# 51-2001-01-10_04_Power_Module_Schematic.net
KiCad netlist of a schematic drawn in Altium Designer
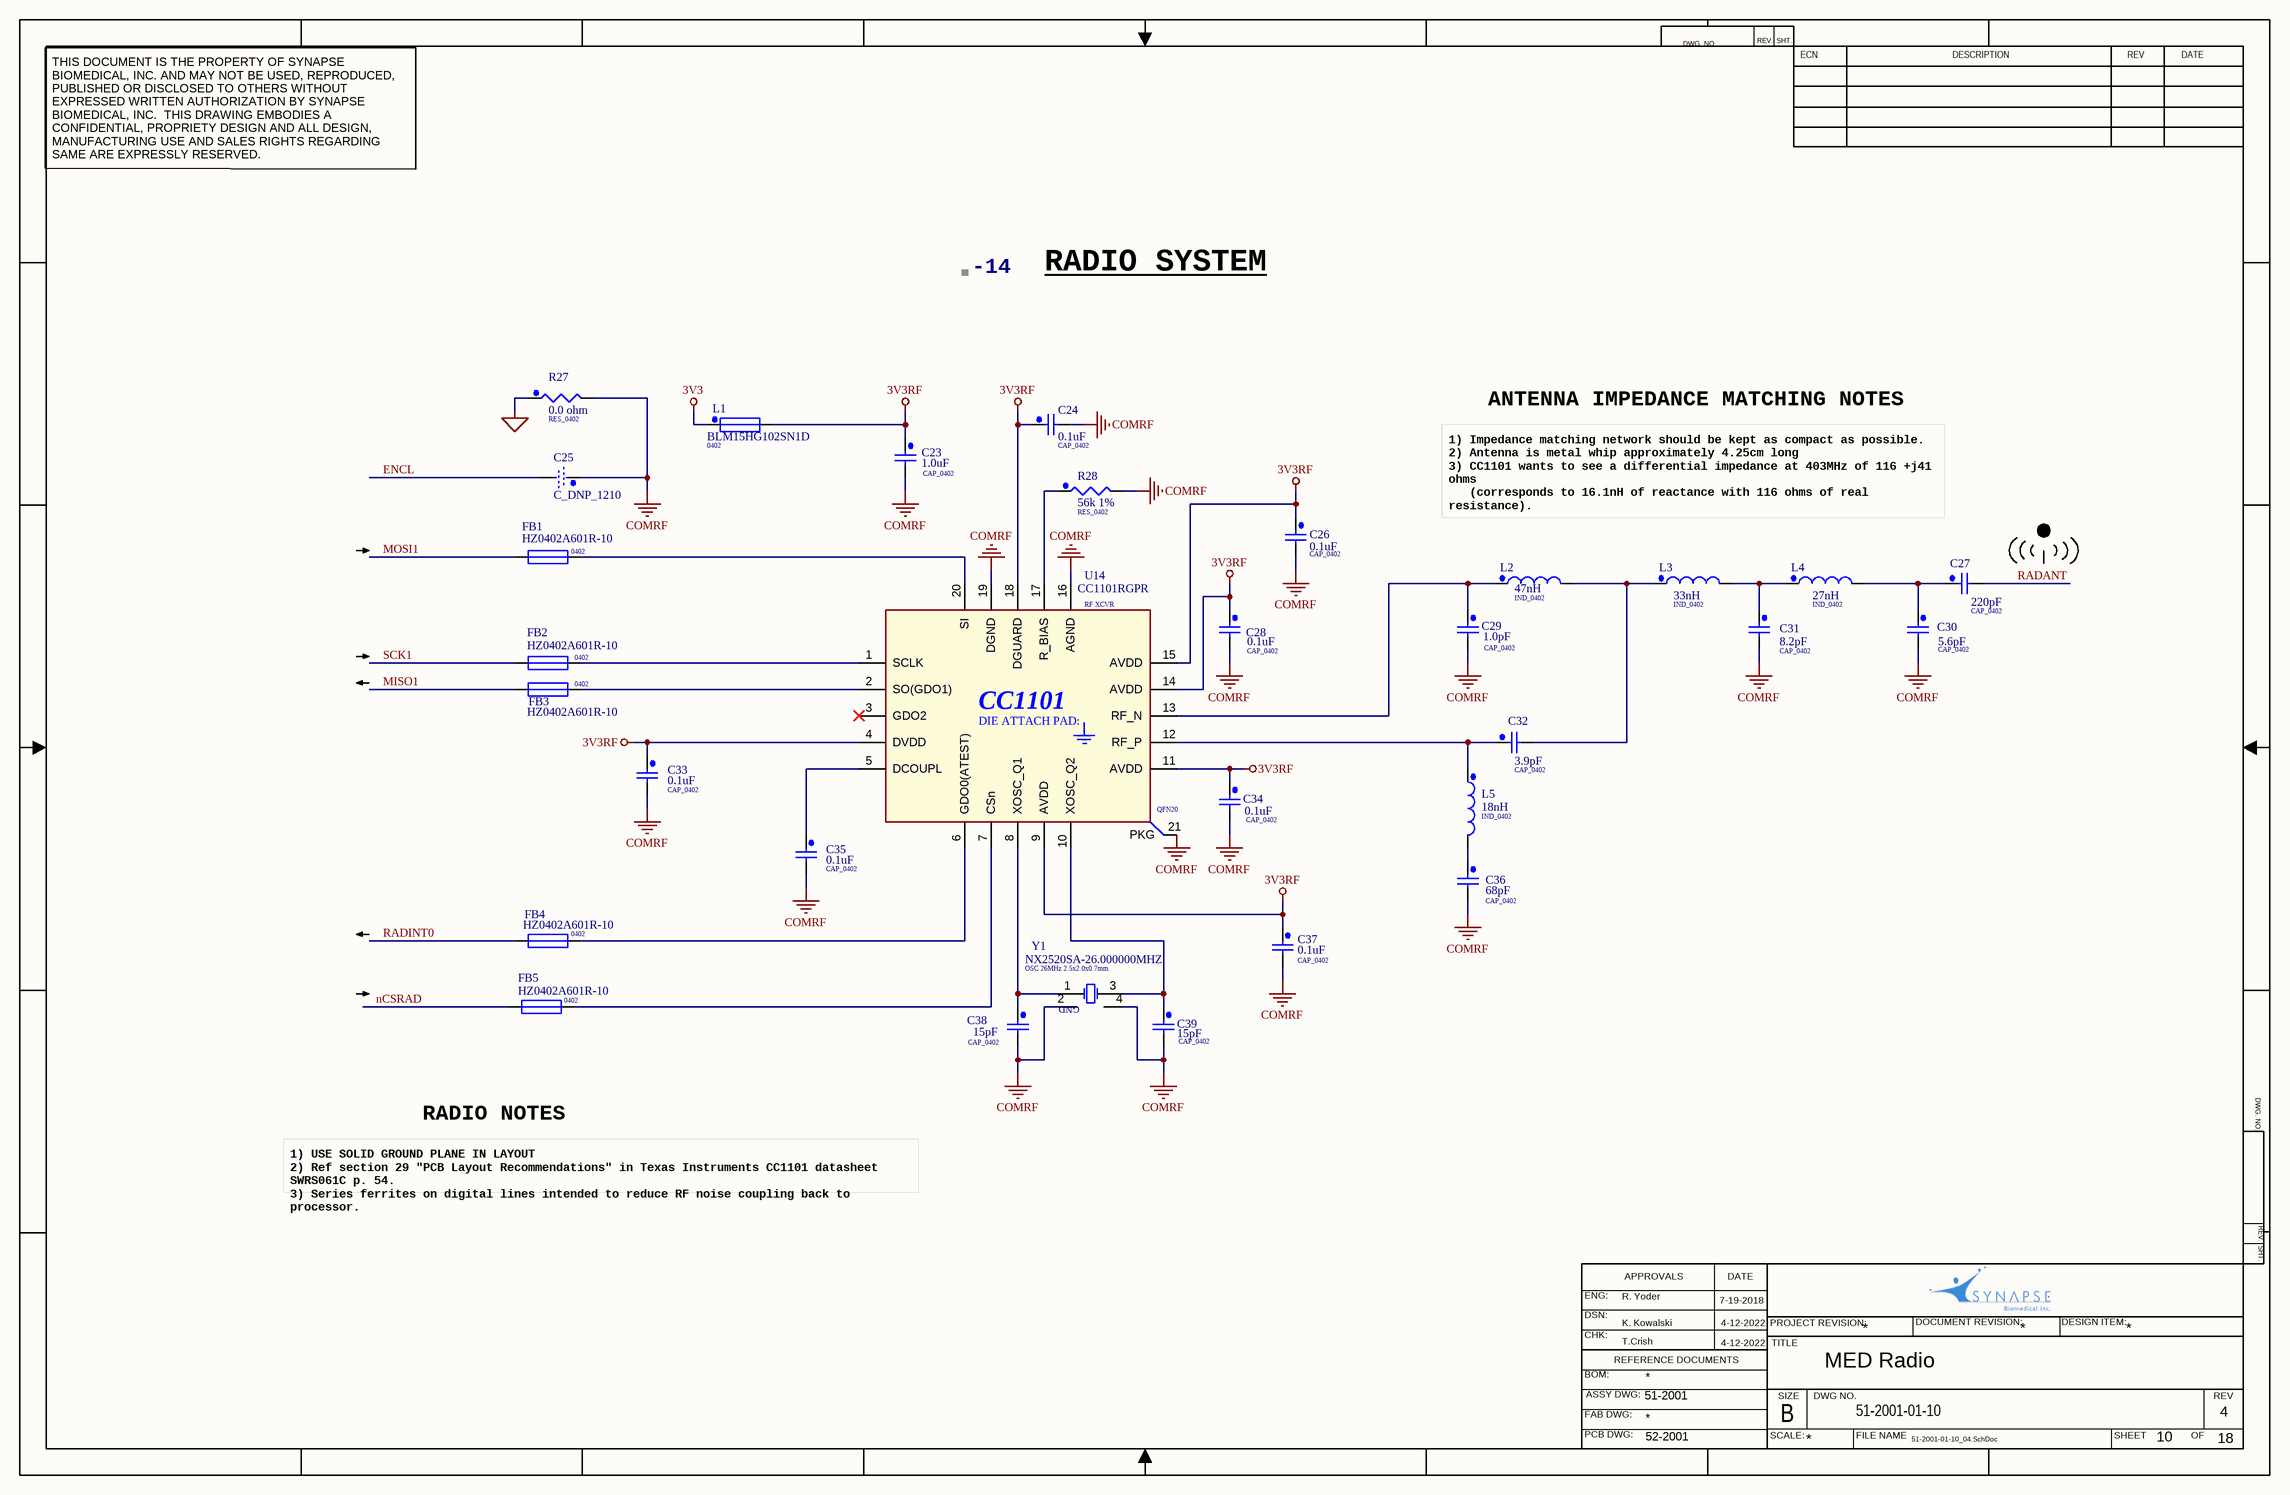
[diagram p0: 51-2001-01-10_04 Power Module Schematic.SchDoc]

(export (version "E")
  (design (tool "Eeschema 10.0.6"))
  (components
    (comp (ref "-14")
      (value "BOM_S1")
      (description "BOM item small graphic")
      (fields (field (name "XDESCRIPTION") "RADIO SYSTEM"))
      (libsource (lib "BOM_sym") (part "BOM_S1"))
    )
    (comp (ref "C23")
      (value "1.0uF")
      (footprint "CAP_0402")
      (description "1.0uF, 6.3V, X5R, 20%, 0402, RoHS")
      (fields
        (field (name "MFR") "Murata Electronics North America")
        (field (name "PACKAGEDESCRIPTION") "CAP_0402")
        (field (name "MPN") "GRM152R60J105ME15D")
      )
      (libsource (lib "NNPS Integrated Parts") (part "ECJ-0EB0J105M"))
    )
    (comp (ref "C24")
      (value "0.1uF")
      (footprint "CAP_0402")
      (description "0.1uF, 16V, X7R, 0402, RoHS")
      (fields
        (field (name "MFR") "Murata")
        (field (name "PACKAGEDESCRIPTION") "CAP_0402")
        (field (name "MPN") "GRM155R71C104KA88D")
      )
      (libsource (lib "NNPS Integrated Parts") (part "GRM155R71C104KA88D"))
    )
    (comp (ref "C25")
      (value "C_DNP_1210")
      (footprint "CAP_1210")
      (fields (field (name "MFR") "DO NOT POPULATE"))
      (libsource (lib "NNPS Integrated Parts") (part "C_DNP_1210"))
    )
    (comp (ref "C26")
      (value "0.1uF")
      (footprint "CAP_0402")
      (description "0.1uF, 16V, X7R, 0402, RoHS")
      (fields
        (field (name "MFR") "Murata")
        (field (name "PACKAGEDESCRIPTION") "CAP_0402")
        (field (name "MPN") "GRM155R71C104KA88D")
      )
      (libsource (lib "NNPS Integrated Parts") (part "GRM155R71C104KA88D"))
    )
    (comp (ref "C27")
      (value "220pF")
      (footprint "CAP_0402")
      (description "220pF, 50V, C0G 5%, 0402, RoHS")
      (fields
        (field (name "MFR") "Murata Electronics North America")
        (field (name "PACKAGEDESCRIPTION") "CAP_0402")
        (field (name "MPN") "GRM1555C1H221JA01")
      )
      (libsource (lib "NNPS Integrated Parts") (part "GRM1555C1H221JA01"))
    )
    (comp (ref "C28")
      (value "0.1uF")
      (footprint "CAP_0402")
      (description "0.1uF, 16V, X7R, 0402, RoHS")
      (fields
        (field (name "MFR") "Murata")
        (field (name "PACKAGEDESCRIPTION") "CAP_0402")
        (field (name "MPN") "GRM155R71C104KA88D")
      )
      (libsource (lib "NNPS Integrated Parts") (part "GRM155R71C104KA88D"))
    )
    (comp (ref "C29")
      (value "1.0pF")
      (footprint "CAP_0402")
      (description "1.0pF, 50V, C0G, 25%, 0402, RoHS")
      (fields
        (field (name "MFR") "Murata Electronics North America")
        (field (name "PACKAGEDESCRIPTION") "CAP_0402")
        (field (name "MPN") "GRM1555C1H1R0CA01D")
      )
      (libsource (lib "NNPS Integrated Parts") (part "GRM1555C1H1R0CA01D"))
    )
    (comp (ref "C30")
      (value "5.6pF")
      (footprint "CAP_0402")
      (description "5.6pF, 50V, C0G, 10%, 0402, RoHS")
      (fields
        (field (name "MFR") "Murata Electronics North America")
        (field (name "PACKAGEDESCRIPTION") "CAP_0402")
        (field (name "MPN") "GRM1555C1H5R6DA01D")
      )
      (libsource (lib "NNPS Integrated Parts") (part "GRM1555C1H5R6DZ01"))
    )
    (comp (ref "C31")
      (value "8.2pF")
      (footprint "CAP_0402")
      (description "8.2pF, 50V, C0G, 5%, 0402, RoHS")
      (fields
        (field (name "MFR") "KEMET")
        (field (name "PACKAGEDESCRIPTION") "CAP_0402")
        (field (name "MPN") "C0402C829J5GACTU")
      )
      (libsource (lib "NNPS Integrated Parts") (part "C1005C0G1H8R2C"))
    )
    (comp (ref "C32")
      (value "3.9pF")
      (footprint "CAP_0402")
      (description "3.9pF, 50V, C0G, 10%, 0402, RoHS")
      (fields
        (field (name "MFR") "Murata Electronics North America")
        (field (name "PACKAGEDESCRIPTION") "CAP_0402")
        (field (name "MPN") "GRM1555C1H3R9CA01D")
      )
      (libsource (lib "NNPS Integrated Parts") (part "GRM1555C1H3R9CZ01"))
    )
    (comp (ref "C33")
      (value "0.1uF")
      (footprint "CAP_0402")
      (description "0.1uF, 16V, X7R, 0402, RoHS")
      (fields
        (field (name "MFR") "Murata")
        (field (name "PACKAGEDESCRIPTION") "CAP_0402")
        (field (name "MPN") "GRM155R71C104KA88D")
      )
      (libsource (lib "NNPS Integrated Parts") (part "GRM155R71C104KA88D"))
    )
    (comp (ref "C34")
      (value "0.1uF")
      (footprint "CAP_0402")
      (description "0.1uF, 16V, X7R, 0402, RoHS")
      (fields
        (field (name "MFR") "Murata")
        (field (name "PACKAGEDESCRIPTION") "CAP_0402")
        (field (name "MPN") "GRM155R71C104KA88D")
      )
      (libsource (lib "NNPS Integrated Parts") (part "GRM155R71C104KA88D"))
    )
    (comp (ref "C35")
      (value "0.1uF")
      (footprint "CAP_0402")
      (description "0.1uF, 16V, X7R, 0402, RoHS")
      (fields
        (field (name "MFR") "Murata")
        (field (name "PACKAGEDESCRIPTION") "CAP_0402")
        (field (name "MPN") "GRM155R71C104KA88D")
      )
      (libsource (lib "NNPS Integrated Parts") (part "GRM155R71C104KA88D"))
    )
    (comp (ref "C36")
      (value "68pF")
      (footprint "CAP_0402")
      (description "68pF, 50V, C0G, 0402, 5%, RoHS")
      (fields
        (field (name "MFR") "Murata Electronics North America")
        (field (name "PACKAGEDESCRIPTION") "CAP_0402")
        (field (name "MPN") "GRM1555C1H680JA01D")
      )
      (libsource (lib "NNPS Integrated Parts") (part "GRM1555C1H680JZ01D"))
    )
    (comp (ref "C37")
      (value "0.1uF")
      (footprint "CAP_0402")
      (description "0.1uF, 16V, X7R, 0402, RoHS")
      (fields
        (field (name "MFR") "Murata")
        (field (name "PACKAGEDESCRIPTION") "CAP_0402")
        (field (name "MPN") "GRM155R71C104KA88D")
      )
      (libsource (lib "NNPS Integrated Parts") (part "GRM155R71C104KA88D"))
    )
    (comp (ref "C38")
      (value "15pF")
      (footprint "CAP_0402")
      (description "15pF, 50V, C0G, 5%, 0402, RoHS")
      (fields
        (field (name "MFR") "Murata Electronics North America")
        (field (name "PACKAGEDESCRIPTION") "CAP_0402")
        (field (name "MPN") "GRM1555C1H150JA01D")
      )
      (libsource (lib "NNPS Integrated Parts") (part "04025A150JAT2A"))
    )
    (comp (ref "C39")
      (value "15pF")
      (footprint "CAP_0402")
      (description "15pF, 50V, C0G, 5%, 0402, RoHS")
      (fields
        (field (name "MFR") "Murata Electronics North America")
        (field (name "PACKAGEDESCRIPTION") "CAP_0402")
        (field (name "MPN") "GRM1555C1H150JA01D")
      )
      (libsource (lib "NNPS Integrated Parts") (part "04025A150JAT2A"))
    )
    (comp (ref "FB1")
      (value "Ferrite 100mA 1ohm")
      (footprint "IND_0402")
      (description "Ferrite, 100mA, 1ohm, 0402, RoHS")
      (fields
        (field (name "MFR") "Laird-Signal Integrity Products")
        (field (name "PACKAGEDESCRIPTION") "0402")
        (field (name "MPN") "HZ0402A601R-10")
      )
      (libsource (lib "NNPS Integrated Parts") (part "HZ0402A601R-10"))
    )
    (comp (ref "FB2")
      (value "Ferrite 100mA 1ohm")
      (footprint "IND_0402")
      (description "Ferrite, 100mA, 1ohm, 0402, RoHS")
      (fields
        (field (name "MFR") "Laird-Signal Integrity Products")
        (field (name "PACKAGEDESCRIPTION") "0402")
        (field (name "MPN") "HZ0402A601R-10")
      )
      (libsource (lib "NNPS Integrated Parts") (part "HZ0402A601R-10"))
    )
    (comp (ref "FB3")
      (value "Ferrite 100mA 1ohm")
      (footprint "IND_0402")
      (description "Ferrite, 100mA, 1ohm, 0402, RoHS")
      (fields
        (field (name "MFR") "Laird-Signal Integrity Products")
        (field (name "PACKAGEDESCRIPTION") "0402")
        (field (name "MPN") "HZ0402A601R-10")
      )
      (libsource (lib "NNPS Integrated Parts") (part "HZ0402A601R-10"))
    )
    (comp (ref "FB4")
      (value "Ferrite 100mA 1ohm")
      (footprint "IND_0402")
      (description "Ferrite, 100mA, 1ohm, 0402, RoHS")
      (fields
        (field (name "MFR") "Laird-Signal Integrity Products")
        (field (name "PACKAGEDESCRIPTION") "0402")
        (field (name "MPN") "HZ0402A601R-10")
      )
      (libsource (lib "NNPS Integrated Parts") (part "HZ0402A601R-10"))
    )
    (comp (ref "FB5")
      (value "Ferrite 100mA 1ohm")
      (footprint "IND_0402")
      (description "Ferrite, 100mA, 1ohm, 0402, RoHS")
      (fields
        (field (name "MFR") "Laird-Signal Integrity Products")
        (field (name "PACKAGEDESCRIPTION") "0402")
        (field (name "MPN") "HZ0402A601R-10")
      )
      (libsource (lib "NNPS Integrated Parts") (part "HZ0402A601R-10"))
    )
    (comp (ref "L1")
      (value "Ferrite 250mA 1.1ohm")
      (footprint "IND_0402")
      (description "Ferrite, 250mA, 1.1ohm, 0402, RoHS")
      (fields
        (field (name "MFR") "Murata")
        (field (name "PACKAGEDESCRIPTION") "0402")
        (field (name "MPN") "BLM15HG102SN1D")
      )
      (libsource (lib "NNPS Integrated Parts") (part "BLM15HG102SN1D"))
    )
    (comp (ref "L2")
      (value "47nH")
      (footprint "IND_0402")
      (description "47nF, 0402, 5%, RoHS")
      (fields
        (field (name "MFR") "Coilcraft")
        (field (name "PACKAGEDESCRIPTION") "IND_0402")
        (field (name "MPN") "0402CS-47NXJLU")
      )
      (libsource (lib "NNPS Integrated Parts") (part "0402CS-47NXJLU"))
    )
    (comp (ref "L3")
      (value "33nH")
      (footprint "IND_0402")
      (description "33nH, 0402, 5%, RoHS")
      (fields
        (field (name "MFR") "Coilcraft")
        (field (name "PACKAGEDESCRIPTION") "IND_0402")
        (field (name "MPN") "0402CS-33NXJLU")
      )
      (libsource (lib "NNPS Integrated Parts") (part "0402CS-33NXJLU"))
    )
    (comp (ref "L4")
      (value "27nH")
      (footprint "IND_0402")
      (description "27nH, 0402, 5%, RoHS")
      (fields
        (field (name "MFR") "Coilcraft")
        (field (name "PACKAGEDESCRIPTION") "IND_0402")
        (field (name "MPN") "0402CS-27NXJLU")
      )
      (libsource (lib "NNPS Integrated Parts") (part "0402CS-27NXJLU"))
    )
    (comp (ref "L5")
      (value "18nH")
      (footprint "IND_0402")
      (description "18nH, 0402, 5%, RoHS")
      (fields
        (field (name "MFR") "Coilcraft")
        (field (name "PACKAGEDESCRIPTION") "IND_0402")
        (field (name "MPN") "0402CS-18NXJLU")
      )
      (libsource (lib "NNPS Integrated Parts") (part "0402CS-18NXJLU"))
    )
    (comp (ref "R27")
      (value "0.0 ohm")
      (footprint "RES_0402")
      (description "0.0 ohm, 1/16W, 0402, RoHS")
      (fields
        (field (name "MFR") "Vishay Dale")
        (field (name "PACKAGEDESCRIPTION") "RES_0402")
        (field (name "MPN") "CRCW04021K00FKED")
      )
      (libsource (lib "NNPS Integrated Parts") (part "MCR01MZPJ000"))
    )
    (comp (ref "R28")
      (value "56k 1%")
      (footprint "RES_0402")
      (description "56k ohm, 1%, 1/16 W, 0402, RoHS")
      (fields
        (field (name "MFR") "Rohm")
        (field (name "PACKAGEDESCRIPTION") "RES_0402")
        (field (name "MPN") "MCR01MZPF5602")
      )
      (libsource (lib "NNPS Integrated Parts") (part "MCR01MZPF5602"))
    )
    (comp (ref "U14")
      (value "RF XCVR")
      (footprint "QFN20")
      (description "Low-Power Sub-1 GHz RF Transceiver, QFN20, RoHS")
      (fields
        (field (name "MFR") "Texas Instruments")
        (field (name "PACKAGEDESCRIPTION") "QFN20")
        (field (name "MPN") "CC1101RGPR")
      )
      (libsource (lib "NNPS Integrated Parts") (part "CC1101RTK"))
    )
    (comp (ref "Y1")
      (value "OSC 26MHz 2.5x2.0x0.7mm")
      (footprint "NX2520SA")
      (description "Xtal, 26MHz,  2.5x2.0x0.7mm, RoHS")
      (fields (field (name "MFR") "NDK") (field (name "MPN") "NX2520SA-26.000000MHZ"))
      (libsource (lib "NNPS Integrated Parts") (part "NX2520SA-26.000000MHZ"))
    )
  )
  (nets
    (net (code "1") (name "/ENCL") (class "Default")
      (node (ref "C25") (pin "2") (pinfunction "2_2") (pintype "passive"))
    )
    (net (code "2") (name "/MISO1") (class "Default")
      (node (ref "FB3") (pin "1") (pinfunction "1_1") (pintype "passive"))
    )
    (net (code "3") (name "/MOSI1") (class "Default")
      (node (ref "FB1") (pin "1") (pinfunction "1_1") (pintype "passive"))
    )
    (net (code "4") (name "/RADANT") (class "Default")
      (node (ref "C27") (pin "2") (pinfunction "2_2") (pintype "passive"))
    )
    (net (code "5") (name "/RADINT0") (class "Default")
      (node (ref "FB4") (pin "1") (pinfunction "1_1") (pintype "passive"))
    )
    (net (code "6") (name "/SCK1") (class "Default")
      (node (ref "FB2") (pin "1") (pinfunction "1_1") (pintype "passive"))
    )
    (net (code "7") (name "/nCSRAD") (class "Default")
      (node (ref "FB5") (pin "1") (pinfunction "1_1") (pintype "passive"))
    )
    (net (code "8") (name "3V3") (class "Default")
      (node (ref "L1") (pin "1") (pinfunction "1_1") (pintype "passive"))
    )
    (net (code "9") (name "3V3RF") (class "Default")
      (node (ref "C23") (pin "1") (pinfunction "1_1") (pintype "passive"))
      (node (ref "C24") (pin "1") (pinfunction "1_1") (pintype "passive"))
      (node (ref "C26") (pin "1") (pinfunction "1_1") (pintype "passive"))
      (node (ref "C28") (pin "1") (pinfunction "1_1") (pintype "passive"))
      (node (ref "C33") (pin "1") (pinfunction "1_1") (pintype "passive"))
      (node (ref "C34") (pin "1") (pinfunction "1_1") (pintype "passive"))
      (node (ref "C37") (pin "1") (pinfunction "1_1") (pintype "passive"))
      (node (ref "L1") (pin "2") (pinfunction "2_2") (pintype "passive"))
      (node (ref "U14") (pin "11") (pinfunction "AVDD_11") (pintype "passive"))
      (node (ref "U14") (pin "14") (pinfunction "AVDD_14") (pintype "passive"))
      (node (ref "U14") (pin "15") (pinfunction "AVDD_15") (pintype "passive"))
      (node (ref "U14") (pin "18") (pinfunction "DGUARD_18") (pintype "passive"))
      (node (ref "U14") (pin "4") (pinfunction "DVDD_4") (pintype "passive"))
      (node (ref "U14") (pin "9") (pinfunction "AVDD_9") (pintype "passive"))
    )
    (net (code "10") (name "COMRF") (class "Default")
      (node (ref "C23") (pin "2") (pinfunction "2_2") (pintype "passive"))
      (node (ref "C24") (pin "2") (pinfunction "2_2") (pintype "passive"))
      (node (ref "C25") (pin "1") (pinfunction "1_1") (pintype "passive"))
      (node (ref "C26") (pin "2") (pinfunction "2_2") (pintype "passive"))
      (node (ref "C28") (pin "2") (pinfunction "2_2") (pintype "passive"))
      (node (ref "C29") (pin "2") (pinfunction "2_2") (pintype "passive"))
      (node (ref "C30") (pin "2") (pinfunction "2_2") (pintype "passive"))
      (node (ref "C31") (pin "2") (pinfunction "2_2") (pintype "passive"))
      (node (ref "C33") (pin "2") (pinfunction "2_2") (pintype "passive"))
      (node (ref "C34") (pin "2") (pinfunction "2_2") (pintype "passive"))
      (node (ref "C35") (pin "2") (pinfunction "2_2") (pintype "passive"))
      (node (ref "C36") (pin "2") (pinfunction "2_2") (pintype "passive"))
      (node (ref "C37") (pin "2") (pinfunction "2_2") (pintype "passive"))
      (node (ref "C38") (pin "2") (pinfunction "2_2") (pintype "passive"))
      (node (ref "C39") (pin "2") (pinfunction "2_2") (pintype "passive"))
      (node (ref "R27") (pin "2") (pinfunction "2_2") (pintype "passive"))
      (node (ref "R28") (pin "2") (pinfunction "2_2") (pintype "passive"))
      (node (ref "U14") (pin "16") (pinfunction "AGND_16") (pintype "passive"))
      (node (ref "U14") (pin "19") (pinfunction "DGND_19") (pintype "passive"))
      (node (ref "U14") (pin "21") (pinfunction "PKG_21") (pintype "power_in"))
      (node (ref "Y1") (pin "2") (pinfunction "GND_2") (pintype "power_in"))
      (node (ref "Y1") (pin "4") (pinfunction "GND_4") (pintype "power_in"))
    )
    (net (code "11") (name "GND") (class "Default")
      (node (ref "R27") (pin "1") (pinfunction "1_1") (pintype "passive"))
    )
    (net (code "12") (name "Net-(C27-Pad1)") (class "Default")
      (node (ref "C27") (pin "1") (pinfunction "1_1") (pintype "passive"))
      (node (ref "C30") (pin "1") (pinfunction "1_1") (pintype "passive"))
      (node (ref "L4") (pin "2") (pinfunction "2_2") (pintype "passive"))
    )
    (net (code "13") (name "Net-(C31-Pad1)") (class "Default")
      (node (ref "C31") (pin "1") (pinfunction "1_1") (pintype "passive"))
      (node (ref "L3") (pin "2") (pinfunction "2_2") (pintype "passive"))
      (node (ref "L4") (pin "1") (pinfunction "1_1") (pintype "passive"))
    )
    (net (code "14") (name "Net-(C32-Pad2)") (class "Default")
      (node (ref "C32") (pin "2") (pinfunction "2_2") (pintype "passive"))
      (node (ref "L2") (pin "2") (pinfunction "2_2") (pintype "passive"))
      (node (ref "L3") (pin "1") (pinfunction "1_1") (pintype "passive"))
    )
    (net (code "15") (name "Net-(C36-Pad1)") (class "Default")
      (node (ref "C36") (pin "1") (pinfunction "1_1") (pintype "passive"))
      (node (ref "L5") (pin "2") (pinfunction "2_2") (pintype "passive"))
    )
    (net (code "16") (name "Net-(U14-CSn)") (class "Default")
      (node (ref "FB5") (pin "2") (pinfunction "2_2") (pintype "passive"))
      (node (ref "U14") (pin "7") (pinfunction "CSn_7") (pintype "passive"))
    )
    (net (code "17") (name "Net-(U14-DCOUPL)") (class "Default")
      (node (ref "C35") (pin "1") (pinfunction "1_1") (pintype "passive"))
      (node (ref "U14") (pin "5") (pinfunction "DCOUPL_5") (pintype "passive"))
    )
    (net (code "18") (name "Net-(U14-GDO0(ATEST))") (class "Default")
      (node (ref "FB4") (pin "2") (pinfunction "2_2") (pintype "passive"))
      (node (ref "U14") (pin "6") (pinfunction "GDO0(ATEST)_6") (pintype "passive"))
    )
    (net (code "19") (name "Net-(U14-RF_N)") (class "Default")
      (node (ref "C29") (pin "1") (pinfunction "1_1") (pintype "passive"))
      (node (ref "L2") (pin "1") (pinfunction "1_1") (pintype "passive"))
      (node (ref "U14") (pin "13") (pinfunction "RF_N_13") (pintype "passive"))
    )
    (net (code "20") (name "Net-(U14-RF_P)") (class "Default")
      (node (ref "C32") (pin "1") (pinfunction "1_1") (pintype "passive"))
      (node (ref "L5") (pin "1") (pinfunction "1_1") (pintype "passive"))
      (node (ref "U14") (pin "12") (pinfunction "RF_P_12") (pintype "passive"))
    )
    (net (code "21") (name "Net-(U14-R_BIAS)") (class "Default")
      (node (ref "R28") (pin "1") (pinfunction "1_1") (pintype "passive"))
      (node (ref "U14") (pin "17") (pinfunction "R_BIAS_17") (pintype "passive"))
    )
    (net (code "22") (name "Net-(U14-SCLK)") (class "Default")
      (node (ref "FB2") (pin "2") (pinfunction "2_2") (pintype "passive"))
      (node (ref "U14") (pin "1") (pinfunction "SCLK_1") (pintype "passive"))
    )
    (net (code "23") (name "Net-(U14-SI)") (class "Default")
      (node (ref "FB1") (pin "2") (pinfunction "2_2") (pintype "passive"))
      (node (ref "U14") (pin "20") (pinfunction "SI_20") (pintype "passive"))
    )
    (net (code "24") (name "Net-(U14-SO(GDO1))") (class "Default")
      (node (ref "FB3") (pin "2") (pinfunction "2_2") (pintype "passive"))
      (node (ref "U14") (pin "2") (pinfunction "SO(GDO1)_2") (pintype "passive"))
    )
    (net (code "25") (name "Net-(U14-XOSC_Q1)") (class "Default")
      (node (ref "C38") (pin "1") (pinfunction "1_1") (pintype "passive"))
      (node (ref "U14") (pin "8") (pinfunction "XOSC_Q1_8") (pintype "passive"))
      (node (ref "Y1") (pin "1") (pinfunction "OSC1_1") (pintype "passive"))
    )
    (net (code "26") (name "Net-(U14-XOSC_Q2)") (class "Default")
      (node (ref "C39") (pin "1") (pinfunction "1_1") (pintype "passive"))
      (node (ref "U14") (pin "10") (pinfunction "XOSC_Q2_10") (pintype "passive"))
      (node (ref "Y1") (pin "3") (pinfunction "OSC2_3") (pintype "passive"))
    )
    (net (code "27") (name "unconnected-(U14-GDO2-Pad3)") (class "Default")
      (node (ref "U14") (pin "3") (pinfunction "GDO2_3") (pintype "passive+no_connect"))
    )
  )
)
